# STOMPBOX_2_0_v3.net
KiCad netlist of a schematic drawn in EAGLE
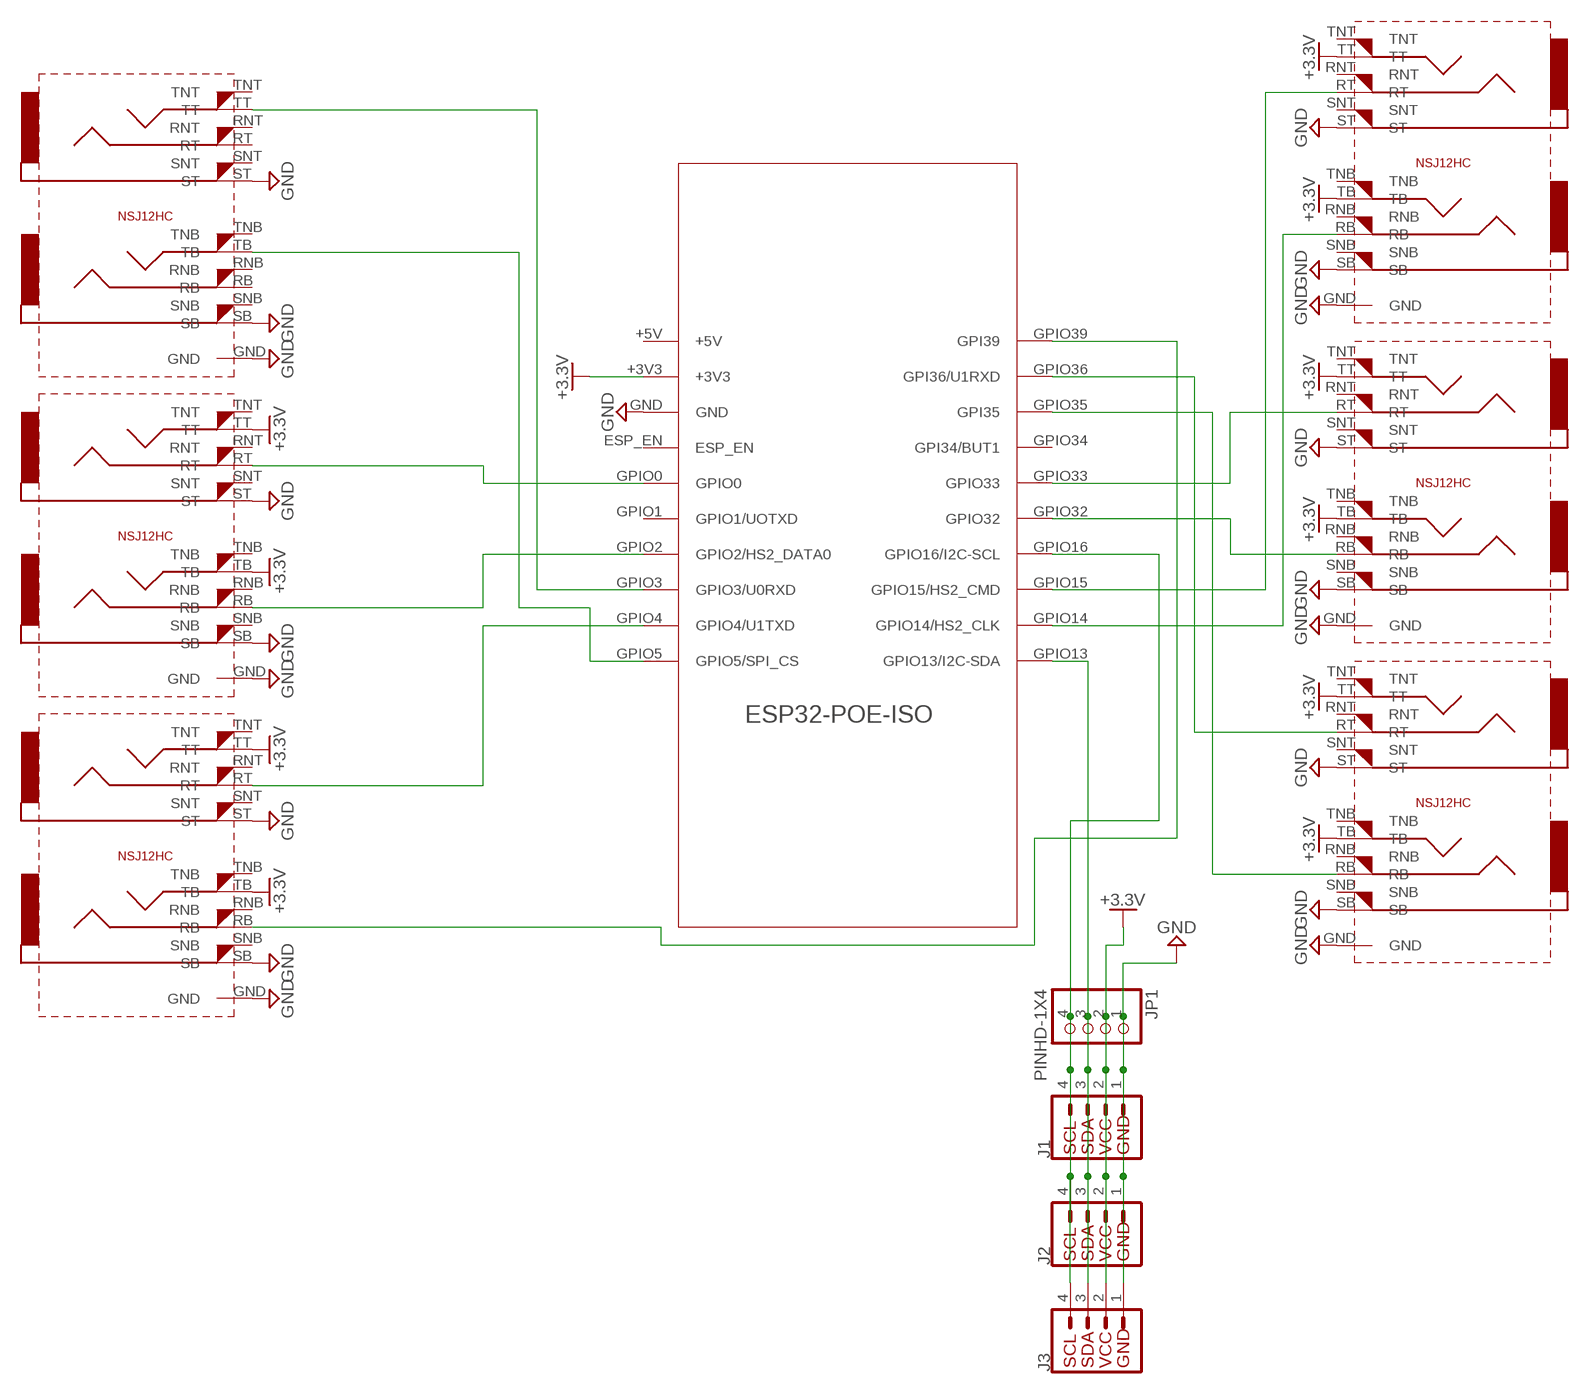
[diagram p0: schematic, sheet 1]

(export (version "E")
  (design (tool "Eeschema 10.0.6"))
  (components
    (comp (ref "J1")
      (value "QWIIC_CONNECTORJS-1MM")
      (footprint "eagle-import:1X04_1MM_RA")
      (libsource (lib "eagle-import") (part "QWIIC_CONNECTORJS-1MM"))
    )
    (comp (ref "J2")
      (value "QWIIC_CONNECTORJS-1MM")
      (footprint "eagle-import:1X04_1MM_RA")
      (libsource (lib "eagle-import") (part "QWIIC_CONNECTORJS-1MM"))
    )
    (comp (ref "J3")
      (value "QWIIC_CONNECTORJS-1MM")
      (footprint "eagle-import:1X04_1MM_RA")
      (libsource (lib "eagle-import") (part "QWIIC_CONNECTORJS-1MM"))
    )
    (comp (ref "JP1")
      (value "PINHD-1X4")
      (footprint "eagle-import:1X04")
      (libsource (lib "eagle-import") (part "PINHD-1X4"))
    )
    (comp (ref "U$1")
      (value "NSJ12HC")
      (footprint "eagle-import:NSJ12HC")
      (libsource (lib "eagle-import") (part "NSJ12HC"))
    )
    (comp (ref "U$2")
      (value "NSJ12HC")
      (footprint "eagle-import:NSJ12HC")
      (libsource (lib "eagle-import") (part "NSJ12HC"))
    )
    (comp (ref "U$3")
      (value "NSJ12HC")
      (footprint "eagle-import:NSJ12HC")
      (libsource (lib "eagle-import") (part "NSJ12HC"))
    )
    (comp (ref "U$4")
      (value "NSJ12HC")
      (footprint "eagle-import:NSJ12HC")
      (libsource (lib "eagle-import") (part "NSJ12HC"))
    )
    (comp (ref "U$5")
      (value "NSJ12HC")
      (footprint "eagle-import:NSJ12HC")
      (libsource (lib "eagle-import") (part "NSJ12HC"))
    )
    (comp (ref "U$6")
      (value "NSJ12HC")
      (footprint "eagle-import:NSJ12HC")
      (libsource (lib "eagle-import") (part "NSJ12HC"))
    )
    (comp (ref "U$8")
      (value "ESP32-POE-ISO")
      (footprint "eagle-import:ESP32-POE-ISO")
      (libsource (lib "eagle-import") (part "ESP32-POE-ISO"))
    )
  )
  (nets
    (net (code "1") (name "+3.3V") (class "Default")
      (node (ref "J1") (pin "2") (pinfunction "VCC_2") (pintype "power_in"))
      (node (ref "J2") (pin "2") (pinfunction "VCC_2") (pintype "power_in"))
      (node (ref "J3") (pin "2") (pinfunction "VCC_2") (pintype "power_in"))
      (node (ref "JP1") (pin "2") (pinfunction "2_2") (pintype "passive"))
      (node (ref "U$2") (pin "TB") (pinfunction "TB_TB") (pintype "bidirectional"))
      (node (ref "U$2") (pin "TT") (pinfunction "TT_TT") (pintype "bidirectional"))
      (node (ref "U$3") (pin "TB") (pinfunction "TB_TB") (pintype "bidirectional"))
      (node (ref "U$3") (pin "TT") (pinfunction "TT_TT") (pintype "bidirectional"))
      (node (ref "U$4") (pin "TB") (pinfunction "TB_TB") (pintype "bidirectional"))
      (node (ref "U$4") (pin "TT") (pinfunction "TT_TT") (pintype "bidirectional"))
      (node (ref "U$5") (pin "TB") (pinfunction "TB_TB") (pintype "bidirectional"))
      (node (ref "U$5") (pin "TT") (pinfunction "TT_TT") (pintype "bidirectional"))
      (node (ref "U$6") (pin "TB") (pinfunction "TB_TB") (pintype "bidirectional"))
      (node (ref "U$6") (pin "TT") (pinfunction "TT_TT") (pintype "bidirectional"))
      (node (ref "U$8") (pin "+3V3") (pinfunction "+3V3_+3V3") (pintype "bidirectional"))
    )
    (net (code "2") (name "GND") (class "Default")
      (node (ref "J1") (pin "1") (pinfunction "GND_1") (pintype "power_in"))
      (node (ref "J2") (pin "1") (pinfunction "GND_1") (pintype "power_in"))
      (node (ref "J3") (pin "1") (pinfunction "GND_1") (pintype "power_in"))
      (node (ref "JP1") (pin "1") (pinfunction "1_1") (pintype "passive"))
      (node (ref "U$1") (pin "GND") (pinfunction "GND_GND") (pintype "bidirectional"))
      (node (ref "U$1") (pin "SB") (pinfunction "SB_SB") (pintype "bidirectional"))
      (node (ref "U$1") (pin "ST") (pinfunction "ST_ST") (pintype "bidirectional"))
      (node (ref "U$2") (pin "GND") (pinfunction "GND_GND") (pintype "bidirectional"))
      (node (ref "U$2") (pin "SB") (pinfunction "SB_SB") (pintype "bidirectional"))
      (node (ref "U$2") (pin "ST") (pinfunction "ST_ST") (pintype "bidirectional"))
      (node (ref "U$3") (pin "GND") (pinfunction "GND_GND") (pintype "bidirectional"))
      (node (ref "U$3") (pin "SB") (pinfunction "SB_SB") (pintype "bidirectional"))
      (node (ref "U$3") (pin "ST") (pinfunction "ST_ST") (pintype "bidirectional"))
      (node (ref "U$4") (pin "GND") (pinfunction "GND_GND") (pintype "bidirectional"))
      (node (ref "U$4") (pin "SB") (pinfunction "SB_SB") (pintype "bidirectional"))
      (node (ref "U$4") (pin "ST") (pinfunction "ST_ST") (pintype "bidirectional"))
      (node (ref "U$5") (pin "GND") (pinfunction "GND_GND") (pintype "bidirectional"))
      (node (ref "U$5") (pin "SB") (pinfunction "SB_SB") (pintype "bidirectional"))
      (node (ref "U$5") (pin "ST") (pinfunction "ST_ST") (pintype "bidirectional"))
      (node (ref "U$6") (pin "GND") (pinfunction "GND_GND") (pintype "bidirectional"))
      (node (ref "U$6") (pin "SB") (pinfunction "SB_SB") (pintype "bidirectional"))
      (node (ref "U$6") (pin "ST") (pinfunction "ST_ST") (pintype "bidirectional"))
      (node (ref "U$8") (pin "GND") (pinfunction "GND_GND") (pintype "bidirectional"))
    )
    (net (code "3") (name "Net-(J1-SCL)") (class "Default")
      (node (ref "J1") (pin "4") (pinfunction "SCL_4") (pintype "passive"))
      (node (ref "J2") (pin "4") (pinfunction "SCL_4") (pintype "passive"))
      (node (ref "J3") (pin "4") (pinfunction "SCL_4") (pintype "passive"))
      (node (ref "JP1") (pin "4") (pinfunction "4_4") (pintype "passive"))
      (node (ref "U$8") (pin "GPIO16") (pinfunction "GPIO16/I2C-SCL_GPIO16") (pintype "bidirectional"))
    )
    (net (code "4") (name "Net-(J1-SDA)") (class "Default")
      (node (ref "J1") (pin "3") (pinfunction "SDA_3") (pintype "passive"))
      (node (ref "J2") (pin "3") (pinfunction "SDA_3") (pintype "passive"))
      (node (ref "J3") (pin "3") (pinfunction "SDA_3") (pintype "passive"))
      (node (ref "JP1") (pin "3") (pinfunction "3_3") (pintype "passive"))
      (node (ref "U$8") (pin "GPIO13") (pinfunction "GPIO13/I2C-SDA_GPIO13") (pintype "bidirectional"))
    )
    (net (code "5") (name "Net-(U$2-PadRT)") (class "Default")
      (node (ref "U$2") (pin "RT") (pinfunction "RT_RT") (pintype "bidirectional"))
      (node (ref "U$8") (pin "GPIO0") (pinfunction "GPIO0_GPIO0") (pintype "bidirectional"))
    )
    (net (code "6") (name "Net-(U$5-PadRB)") (class "Default")
      (node (ref "U$5") (pin "RB") (pinfunction "RB_RB") (pintype "bidirectional"))
      (node (ref "U$8") (pin "GPIO32") (pinfunction "GPIO32_GPIO32") (pintype "bidirectional"))
    )
    (net (code "7") (name "Net-(U$5-PadRT)") (class "Default")
      (node (ref "U$5") (pin "RT") (pinfunction "RT_RT") (pintype "bidirectional"))
      (node (ref "U$8") (pin "GPIO33") (pinfunction "GPIO33_GPIO33") (pintype "bidirectional"))
    )
    (net (code "8") (name "Net-(U$8-GPI35)") (class "Default")
      (node (ref "U$4") (pin "RB") (pinfunction "RB_RB") (pintype "bidirectional"))
      (node (ref "U$8") (pin "GPIO35") (pinfunction "GPI35_GPIO35") (pintype "bidirectional"))
    )
    (net (code "9") (name "Net-(U$8-GPI36{slash}U1RXD)") (class "Default")
      (node (ref "U$4") (pin "RT") (pinfunction "RT_RT") (pintype "bidirectional"))
      (node (ref "U$8") (pin "GPIO36") (pinfunction "GPI36/U1RXD_GPIO36") (pintype "bidirectional"))
    )
    (net (code "10") (name "Net-(U$8-GPI39)") (class "Default")
      (node (ref "U$3") (pin "RB") (pinfunction "RB_RB") (pintype "bidirectional"))
      (node (ref "U$8") (pin "GPIO39") (pinfunction "GPI39_GPIO39") (pintype "bidirectional"))
    )
    (net (code "11") (name "Net-(U$8-GPIO2{slash}HS2_DATA0)") (class "Default")
      (node (ref "U$2") (pin "RB") (pinfunction "RB_RB") (pintype "bidirectional"))
      (node (ref "U$8") (pin "GPIO2") (pinfunction "GPIO2/HS2_DATA0_GPIO2") (pintype "bidirectional"))
    )
    (net (code "12") (name "Net-(U$8-GPIO3{slash}U0RXD)") (class "Default")
      (node (ref "U$1") (pin "TT") (pinfunction "TT_TT") (pintype "bidirectional"))
      (node (ref "U$8") (pin "GPIO3") (pinfunction "GPIO3/U0RXD_GPIO3") (pintype "bidirectional"))
    )
    (net (code "13") (name "Net-(U$8-GPIO4{slash}U1TXD)") (class "Default")
      (node (ref "U$3") (pin "RT") (pinfunction "RT_RT") (pintype "bidirectional"))
      (node (ref "U$8") (pin "GPIO4") (pinfunction "GPIO4/U1TXD_GPIO4") (pintype "bidirectional"))
    )
    (net (code "14") (name "Net-(U$8-GPIO5{slash}SPI_CS)") (class "Default")
      (node (ref "U$1") (pin "TB") (pinfunction "TB_TB") (pintype "bidirectional"))
      (node (ref "U$8") (pin "GPIO5") (pinfunction "GPIO5/SPI_CS_GPIO5") (pintype "bidirectional"))
    )
    (net (code "15") (name "Net-(U$8-GPIO14{slash}HS2_CLK)") (class "Default")
      (node (ref "U$6") (pin "RB") (pinfunction "RB_RB") (pintype "bidirectional"))
      (node (ref "U$8") (pin "GPIO14") (pinfunction "GPIO14/HS2_CLK_GPIO14") (pintype "bidirectional"))
    )
    (net (code "16") (name "Net-(U$8-GPIO15{slash}HS2_CMD)") (class "Default")
      (node (ref "U$6") (pin "RT") (pinfunction "RT_RT") (pintype "bidirectional"))
      (node (ref "U$8") (pin "GPIO15") (pinfunction "GPIO15/HS2_CMD_GPIO15") (pintype "bidirectional"))
    )
    (net (code "17") (name "unconnected-(U$1-PadRB)") (class "Default")
      (node (ref "U$1") (pin "RB") (pinfunction "RB_RB") (pintype "bidirectional"))
    )
    (net (code "18") (name "unconnected-(U$1-PadRNB)") (class "Default")
      (node (ref "U$1") (pin "RNB") (pinfunction "RNB_RNB") (pintype "bidirectional"))
    )
    (net (code "19") (name "unconnected-(U$1-PadRNT)") (class "Default")
      (node (ref "U$1") (pin "RNT") (pinfunction "RNT_RNT") (pintype "bidirectional"))
    )
    (net (code "20") (name "unconnected-(U$1-PadRT)") (class "Default")
      (node (ref "U$1") (pin "RT") (pinfunction "RT_RT") (pintype "bidirectional"))
    )
    (net (code "21") (name "unconnected-(U$1-PadSNB)") (class "Default")
      (node (ref "U$1") (pin "SNB") (pinfunction "SNB_SNB") (pintype "bidirectional"))
    )
    (net (code "22") (name "unconnected-(U$1-PadSNT)") (class "Default")
      (node (ref "U$1") (pin "SNT") (pinfunction "SNT_SNT") (pintype "bidirectional"))
    )
    (net (code "23") (name "unconnected-(U$1-PadTNB)") (class "Default")
      (node (ref "U$1") (pin "TNB") (pinfunction "TNB_TNB") (pintype "bidirectional"))
    )
    (net (code "24") (name "unconnected-(U$1-PadTNT)") (class "Default")
      (node (ref "U$1") (pin "TNT") (pinfunction "TNT_TNT") (pintype "bidirectional"))
    )
    (net (code "25") (name "unconnected-(U$2-PadRNB)") (class "Default")
      (node (ref "U$2") (pin "RNB") (pinfunction "RNB_RNB") (pintype "bidirectional"))
    )
    (net (code "26") (name "unconnected-(U$2-PadRNT)") (class "Default")
      (node (ref "U$2") (pin "RNT") (pinfunction "RNT_RNT") (pintype "bidirectional"))
    )
    (net (code "27") (name "unconnected-(U$2-PadSNB)") (class "Default")
      (node (ref "U$2") (pin "SNB") (pinfunction "SNB_SNB") (pintype "bidirectional"))
    )
    (net (code "28") (name "unconnected-(U$2-PadSNT)") (class "Default")
      (node (ref "U$2") (pin "SNT") (pinfunction "SNT_SNT") (pintype "bidirectional"))
    )
    (net (code "29") (name "unconnected-(U$2-PadTNB)") (class "Default")
      (node (ref "U$2") (pin "TNB") (pinfunction "TNB_TNB") (pintype "bidirectional"))
    )
    (net (code "30") (name "unconnected-(U$2-PadTNT)") (class "Default")
      (node (ref "U$2") (pin "TNT") (pinfunction "TNT_TNT") (pintype "bidirectional"))
    )
    (net (code "31") (name "unconnected-(U$3-PadRNB)") (class "Default")
      (node (ref "U$3") (pin "RNB") (pinfunction "RNB_RNB") (pintype "bidirectional"))
    )
    (net (code "32") (name "unconnected-(U$3-PadRNT)") (class "Default")
      (node (ref "U$3") (pin "RNT") (pinfunction "RNT_RNT") (pintype "bidirectional"))
    )
    (net (code "33") (name "unconnected-(U$3-PadSNB)") (class "Default")
      (node (ref "U$3") (pin "SNB") (pinfunction "SNB_SNB") (pintype "bidirectional"))
    )
    (net (code "34") (name "unconnected-(U$3-PadSNT)") (class "Default")
      (node (ref "U$3") (pin "SNT") (pinfunction "SNT_SNT") (pintype "bidirectional"))
    )
    (net (code "35") (name "unconnected-(U$3-PadTNB)") (class "Default")
      (node (ref "U$3") (pin "TNB") (pinfunction "TNB_TNB") (pintype "bidirectional"))
    )
    (net (code "36") (name "unconnected-(U$3-PadTNT)") (class "Default")
      (node (ref "U$3") (pin "TNT") (pinfunction "TNT_TNT") (pintype "bidirectional"))
    )
    (net (code "37") (name "unconnected-(U$4-PadRNB)") (class "Default")
      (node (ref "U$4") (pin "RNB") (pinfunction "RNB_RNB") (pintype "bidirectional"))
    )
    (net (code "38") (name "unconnected-(U$4-PadRNT)") (class "Default")
      (node (ref "U$4") (pin "RNT") (pinfunction "RNT_RNT") (pintype "bidirectional"))
    )
    (net (code "39") (name "unconnected-(U$4-PadSNB)") (class "Default")
      (node (ref "U$4") (pin "SNB") (pinfunction "SNB_SNB") (pintype "bidirectional"))
    )
    (net (code "40") (name "unconnected-(U$4-PadSNT)") (class "Default")
      (node (ref "U$4") (pin "SNT") (pinfunction "SNT_SNT") (pintype "bidirectional"))
    )
    (net (code "41") (name "unconnected-(U$4-PadTNB)") (class "Default")
      (node (ref "U$4") (pin "TNB") (pinfunction "TNB_TNB") (pintype "bidirectional"))
    )
    (net (code "42") (name "unconnected-(U$4-PadTNT)") (class "Default")
      (node (ref "U$4") (pin "TNT") (pinfunction "TNT_TNT") (pintype "bidirectional"))
    )
    (net (code "43") (name "unconnected-(U$5-PadRNB)") (class "Default")
      (node (ref "U$5") (pin "RNB") (pinfunction "RNB_RNB") (pintype "bidirectional"))
    )
    (net (code "44") (name "unconnected-(U$5-PadRNT)") (class "Default")
      (node (ref "U$5") (pin "RNT") (pinfunction "RNT_RNT") (pintype "bidirectional"))
    )
    (net (code "45") (name "unconnected-(U$5-PadSNB)") (class "Default")
      (node (ref "U$5") (pin "SNB") (pinfunction "SNB_SNB") (pintype "bidirectional"))
    )
    (net (code "46") (name "unconnected-(U$5-PadSNT)") (class "Default")
      (node (ref "U$5") (pin "SNT") (pinfunction "SNT_SNT") (pintype "bidirectional"))
    )
    (net (code "47") (name "unconnected-(U$5-PadTNB)") (class "Default")
      (node (ref "U$5") (pin "TNB") (pinfunction "TNB_TNB") (pintype "bidirectional"))
    )
    (net (code "48") (name "unconnected-(U$5-PadTNT)") (class "Default")
      (node (ref "U$5") (pin "TNT") (pinfunction "TNT_TNT") (pintype "bidirectional"))
    )
    (net (code "49") (name "unconnected-(U$6-PadRNB)") (class "Default")
      (node (ref "U$6") (pin "RNB") (pinfunction "RNB_RNB") (pintype "bidirectional"))
    )
    (net (code "50") (name "unconnected-(U$6-PadRNT)") (class "Default")
      (node (ref "U$6") (pin "RNT") (pinfunction "RNT_RNT") (pintype "bidirectional"))
    )
    (net (code "51") (name "unconnected-(U$6-PadSNB)") (class "Default")
      (node (ref "U$6") (pin "SNB") (pinfunction "SNB_SNB") (pintype "bidirectional"))
    )
    (net (code "52") (name "unconnected-(U$6-PadSNT)") (class "Default")
      (node (ref "U$6") (pin "SNT") (pinfunction "SNT_SNT") (pintype "bidirectional"))
    )
    (net (code "53") (name "unconnected-(U$6-PadTNB)") (class "Default")
      (node (ref "U$6") (pin "TNB") (pinfunction "TNB_TNB") (pintype "bidirectional"))
    )
    (net (code "54") (name "unconnected-(U$6-PadTNT)") (class "Default")
      (node (ref "U$6") (pin "TNT") (pinfunction "TNT_TNT") (pintype "bidirectional"))
    )
    (net (code "55") (name "unconnected-(U$8-GPI34{slash}BUT1-PadGPIO34)") (class "Default")
      (node (ref "U$8") (pin "GPIO34") (pinfunction "GPI34/BUT1_GPIO34") (pintype "bidirectional"))
    )
    (net (code "56") (name "unconnected-(U$8-GPIO1{slash}UOTXD-PadGPIO1)") (class "Default")
      (node (ref "U$8") (pin "GPIO1") (pinfunction "GPIO1/UOTXD_GPIO1") (pintype "bidirectional"))
    )
    (net (code "57") (name "unconnected-(U$8-Pad+5V)") (class "Default")
      (node (ref "U$8") (pin "+5V") (pinfunction "+5V_+5V") (pintype "bidirectional"))
    )
    (net (code "58") (name "unconnected-(U$8-PadESP_EN)") (class "Default")
      (node (ref "U$8") (pin "ESP_EN") (pinfunction "ESP_EN_ESP_EN") (pintype "bidirectional"))
    )
  )
)
